# 7-RES_CHECK.net
KiCad netlist of a schematic drawn in Altium Designer
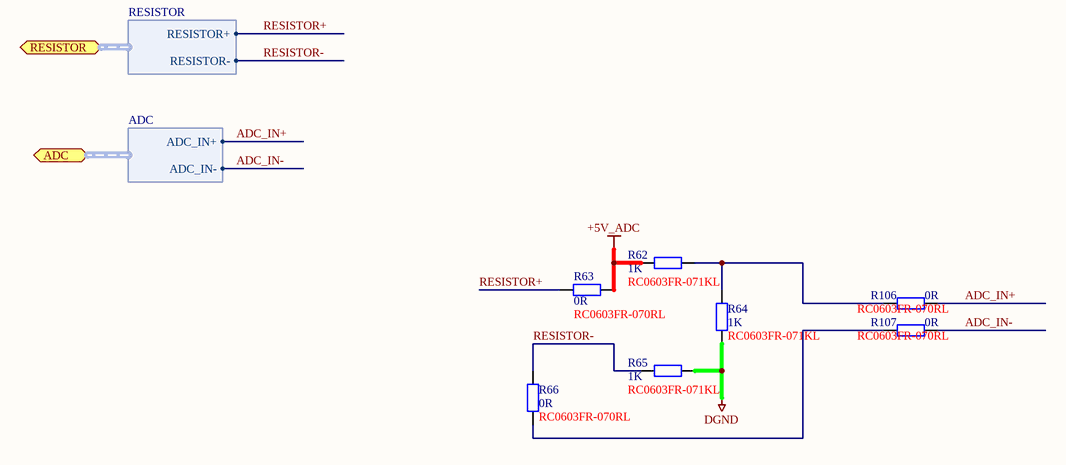
[diagram p0: 7-RES_CHECK.SchDoc]

(export (version "E")
  (design (tool "Eeschema 10.0.6"))
  (components
    (comp (ref "R62")
      (value "1K")
      (footprint "CC0603")
      (description "Resistor")
      (fields (field (name "TYPE NO.") "RC0603FR-071KL"))
      (libsource (lib "") (part "Res2_1"))
    )
    (comp (ref "R63")
      (value "0R")
      (footprint "CC0603")
      (description "Resistor")
      (fields (field (name "TYPE NO.") "RC0603FR-070RL"))
      (libsource (lib "") (part "Res2_2"))
    )
    (comp (ref "R64")
      (value "1K")
      (footprint "CC0603")
      (description "Resistor")
      (fields (field (name "TYPE NO.") "RC0603FR-071KL"))
      (libsource (lib "Miscellaneous Devices") (part "Res2"))
    )
    (comp (ref "R65")
      (value "1K")
      (footprint "CC0603")
      (description "Resistor")
      (fields (field (name "TYPE NO.") "RC0603FR-071KL"))
      (libsource (lib "") (part "Res2_1"))
    )
    (comp (ref "R66")
      (value "0R")
      (footprint "CC0603")
      (description "Resistor")
      (fields (field (name "TYPE NO.") "RC0603FR-070RL"))
      (libsource (lib "Miscellaneous Devices") (part "Res2"))
    )
    (comp (ref "R106")
      (value "0R")
      (footprint "CC0603")
      (description "Resistor")
      (fields (field (name "TYPE NO.") "RC0603FR-070RL"))
      (libsource (lib "") (part "Res2_1"))
    )
    (comp (ref "R107")
      (value "0R")
      (footprint "CC0603")
      (description "Resistor")
      (fields (field (name "TYPE NO.") "RC0603FR-070RL"))
      (libsource (lib "") (part "Res2_1"))
    )
  )
  (nets
    (net (code "3") (name "+5V_ADC") (class "Default")
      (node (ref "R62") (pin "2") (pinfunction "2_2") (pintype "passive"))
      (node (ref "R63") (pin "2") (pinfunction "2_2") (pintype "passive"))
    )
    (net (code "4") (name "/ADC_IN+") (class "Default")
      (node (ref "R106") (pin "1") (pinfunction "1_1") (pintype "passive"))
    )
    (net (code "5") (name "/ADC_IN-") (class "Default")
      (node (ref "R107") (pin "1") (pinfunction "1_1") (pintype "passive"))
    )
    (net (code "6") (name "/RESISTOR+") (class "Default")
      (node (ref "R63") (pin "1") (pinfunction "1_1") (pintype "passive"))
    )
    (net (code "7") (name "/RESISTOR-") (class "Default")
      (node (ref "R65") (pin "2") (pinfunction "2_2") (pintype "passive"))
      (node (ref "R66") (pin "1") (pinfunction "1_1") (pintype "passive"))
    )
    (net (code "10") (name "DGND") (class "Default")
      (node (ref "R64") (pin "2") (pinfunction "2_2") (pintype "passive"))
      (node (ref "R65") (pin "1") (pinfunction "1_1") (pintype "passive"))
    )
    (net (code "11") (name "Net-(R106-Pad2)") (class "Default")
      (node (ref "R106") (pin "2") (pinfunction "2_2") (pintype "passive"))
      (node (ref "R62") (pin "1") (pinfunction "1_1") (pintype "passive"))
      (node (ref "R64") (pin "1") (pinfunction "1_1") (pintype "passive"))
    )
    (net (code "12") (name "Net-(R107-Pad2)") (class "Default")
      (node (ref "R107") (pin "2") (pinfunction "2_2") (pintype "passive"))
      (node (ref "R66") (pin "2") (pinfunction "2_2") (pintype "passive"))
    )
  )
)
